# DE-110817_01.net
KiCad netlist of a schematic drawn in Altium Designer
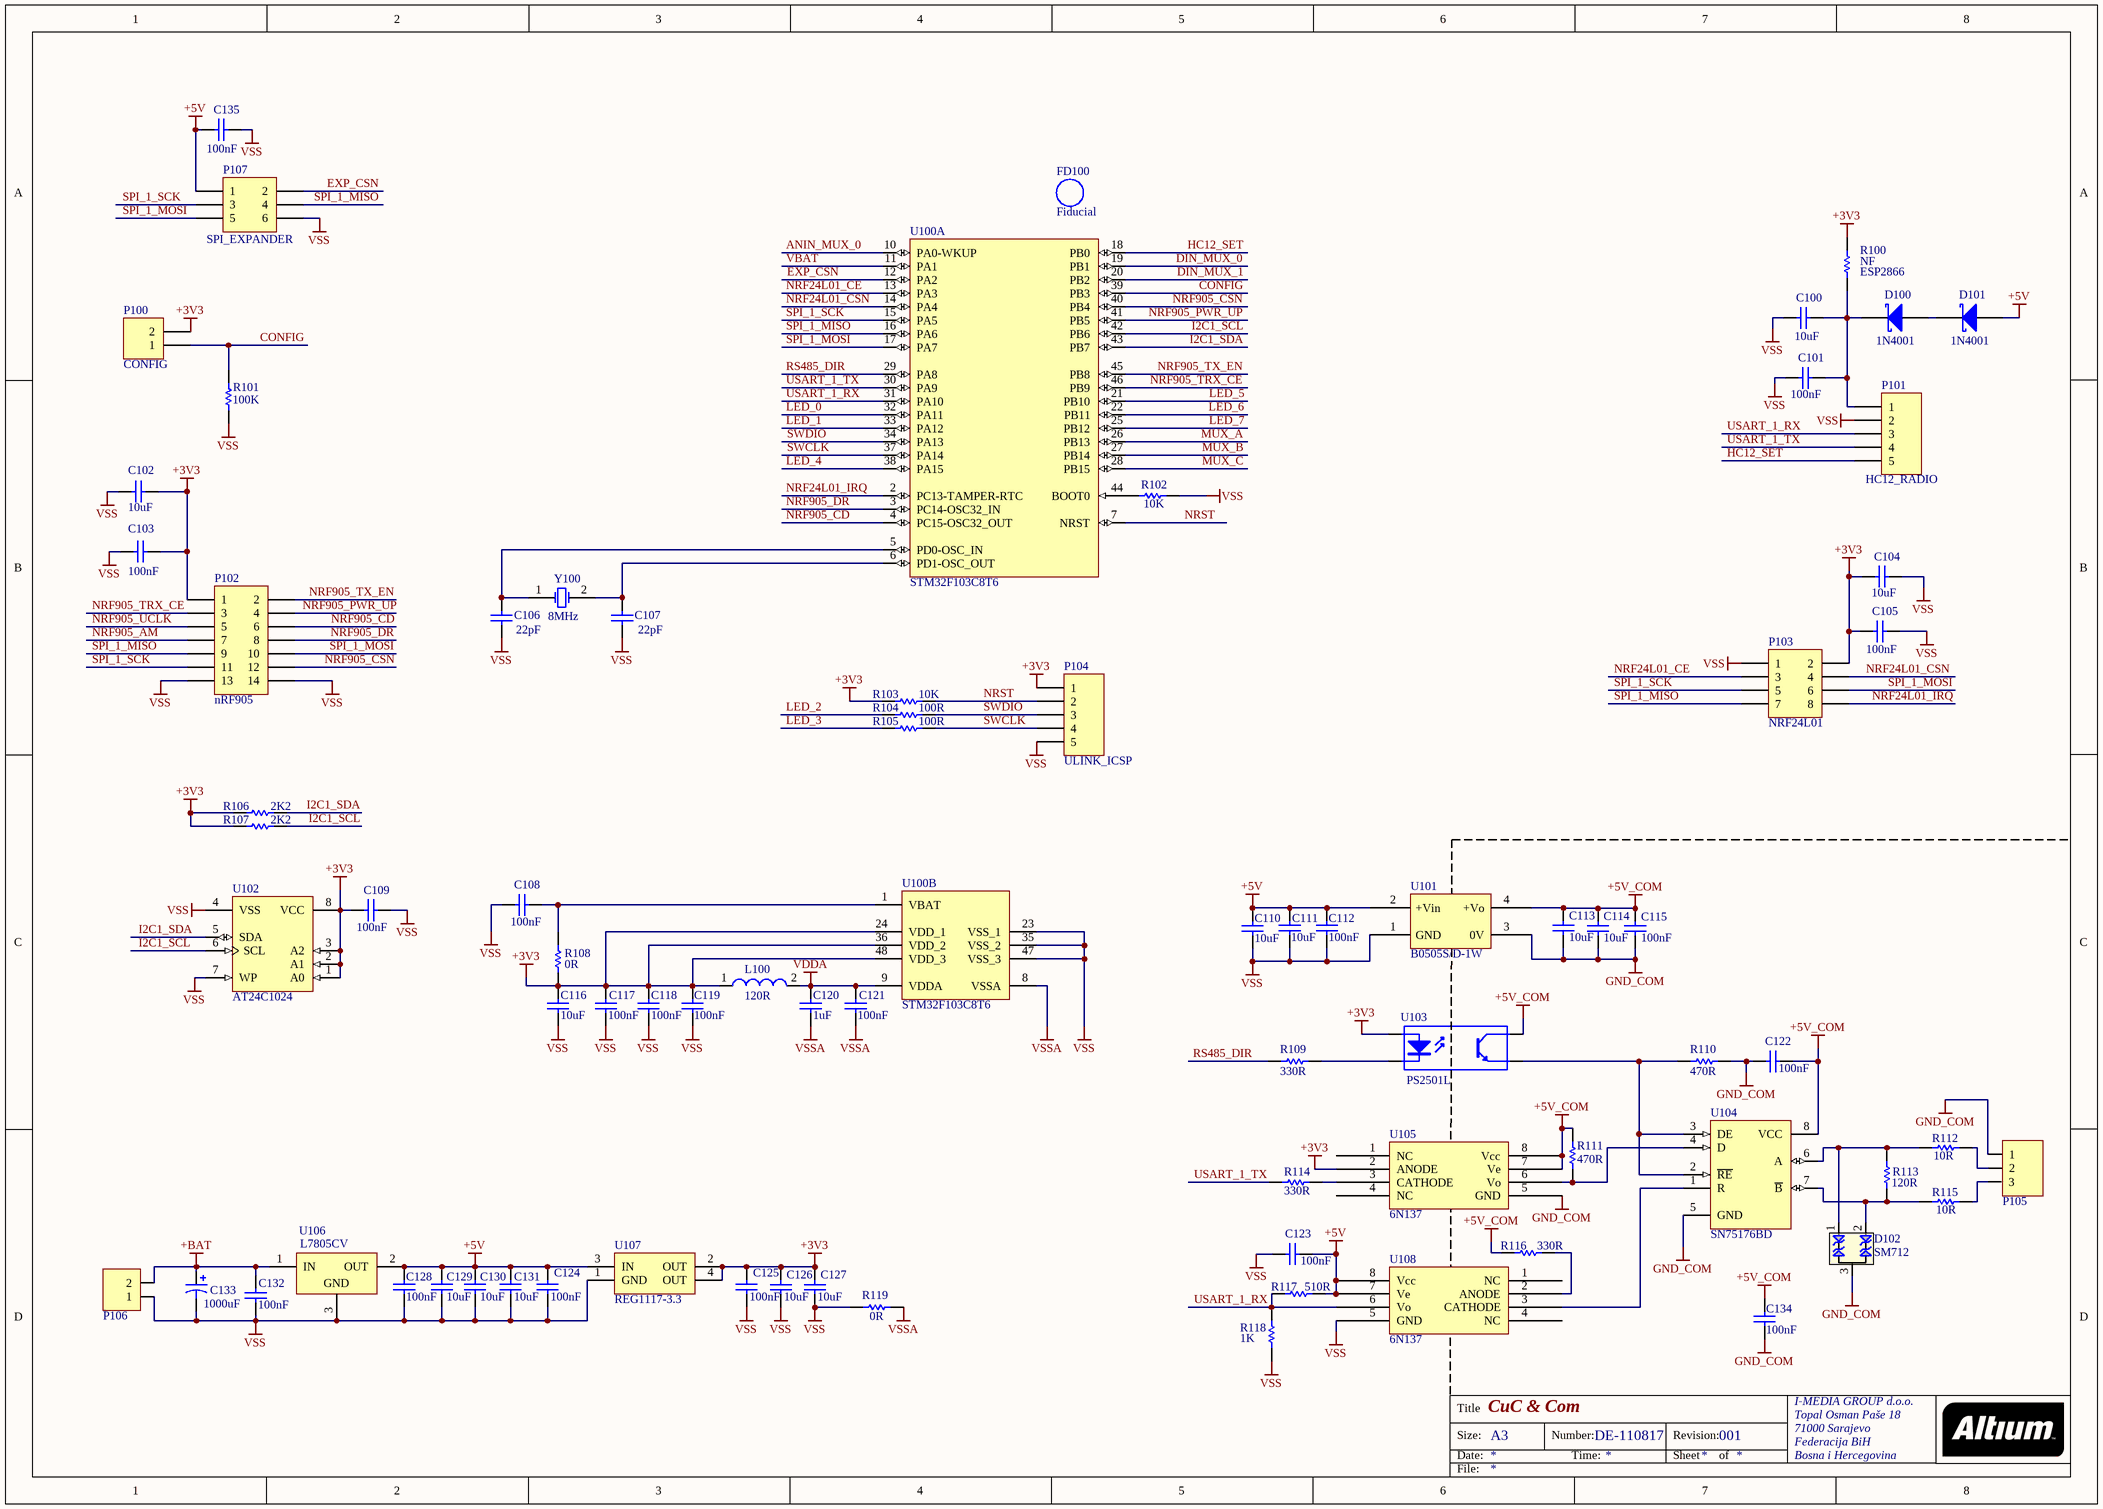
[diagram p0: DE-110817_01.SchDoc]

(export (version "E")
  (design (tool "Eeschema 10.0.6"))
  (components
    (comp (ref "C100")
      (value "10uF")
      (footprint "0805")
      (description "Ceramic Chip Capacitor - Standard")
      (fields (field (name "PUBLISHER") "Altium Limited"))
      (libsource (lib "KEMET Chip Capacitor") (part "C0805"))
    )
    (comp (ref "C101")
      (value "100nF")
      (footprint "0603")
      (description "Ceramic Chip Capacitor - Standard")
      (fields (field (name "PUBLISHER") "Altium Limited"))
      (libsource (lib "KEMET Chip Capacitor") (part "C0603"))
    )
    (comp (ref "C102")
      (value "10uF")
      (footprint "0805")
      (description "Ceramic Chip Capacitor - Standard")
      (fields (field (name "PUBLISHER") "Altium Limited"))
      (libsource (lib "KEMET Chip Capacitor") (part "C0805"))
    )
    (comp (ref "C103")
      (value "100nF")
      (footprint "0603")
      (description "Ceramic Chip Capacitor - Standard")
      (fields (field (name "PUBLISHER") "Altium Limited"))
      (libsource (lib "KEMET Chip Capacitor") (part "C0603"))
    )
    (comp (ref "C104")
      (value "10uF")
      (footprint "0805")
      (description "Ceramic Chip Capacitor - Standard")
      (fields (field (name "PUBLISHER") "Altium Limited"))
      (libsource (lib "KEMET Chip Capacitor") (part "C0805"))
    )
    (comp (ref "C105")
      (value "100nF")
      (footprint "0603")
      (description "Ceramic Chip Capacitor - Standard")
      (fields (field (name "PUBLISHER") "Altium Limited"))
      (libsource (lib "KEMET Chip Capacitor") (part "C0603"))
    )
    (comp (ref "C106")
      (value "22pF")
      (footprint "0603")
      (description "Ceramic Chip Capacitor - Standard")
      (fields (field (name "PUBLISHER") "Altium Limited"))
      (libsource (lib "KEMET Chip Capacitor") (part "C0603"))
    )
    (comp (ref "C107")
      (value "22pF")
      (footprint "0603")
      (description "Ceramic Chip Capacitor - Standard")
      (fields (field (name "PUBLISHER") "Altium Limited"))
      (libsource (lib "KEMET Chip Capacitor") (part "C0603"))
    )
    (comp (ref "C108")
      (value "100nF")
      (footprint "0603")
      (description "Ceramic Chip Capacitor - Standard")
      (fields (field (name "PUBLISHER") "Altium Limited"))
      (libsource (lib "KEMET Chip Capacitor") (part "C0603"))
    )
    (comp (ref "C109")
      (value "100nF")
      (footprint "0603")
      (description "Ceramic Chip Capacitor - Standard")
      (fields (field (name "PUBLISHER") "Altium Limited"))
      (libsource (lib "DE-251215") (part "C0603"))
    )
    (comp (ref "C110")
      (value "10uF")
      (footprint "0805")
      (description "Ceramic Chip Capacitor - Standard")
      (fields (field (name "PUBLISHER") "Altium Limited"))
      (libsource (lib "DE-110817") (part "C0805"))
    )
    (comp (ref "C111")
      (value "10uF")
      (footprint "0805")
      (description "Ceramic Chip Capacitor - Standard")
      (fields (field (name "PUBLISHER") "Altium Limited"))
      (libsource (lib "DE-110817") (part "C0805"))
    )
    (comp (ref "C112")
      (value "100nF")
      (footprint "0603")
      (description "Ceramic Chip Capacitor - Standard")
      (fields (field (name "PUBLISHER") "Altium Limited"))
      (libsource (lib "DE-110817") (part "C0603"))
    )
    (comp (ref "C113")
      (value "10uF")
      (footprint "0805")
      (description "Ceramic Chip Capacitor - Standard")
      (fields (field (name "PUBLISHER") "Altium Limited"))
      (libsource (lib "DE-110817") (part "C0805"))
    )
    (comp (ref "C114")
      (value "10uF")
      (footprint "0805")
      (description "Ceramic Chip Capacitor - Standard")
      (fields (field (name "PUBLISHER") "Altium Limited"))
      (libsource (lib "DE-110817") (part "C0805"))
    )
    (comp (ref "C115")
      (value "100nF")
      (footprint "0603")
      (description "Ceramic Chip Capacitor - Standard")
      (fields (field (name "PUBLISHER") "Altium Limited"))
      (libsource (lib "DE-110817") (part "C0603"))
    )
    (comp (ref "C116")
      (value "10uF")
      (footprint "0805")
      (description "Ceramic Chip Capacitor - Standard")
      (fields (field (name "PUBLISHER") "Altium Limited"))
      (libsource (lib "KEMET Chip Capacitor") (part "C0805"))
    )
    (comp (ref "C117")
      (value "100nF")
      (footprint "0603")
      (description "Ceramic Chip Capacitor - Standard")
      (fields (field (name "PUBLISHER") "Altium Limited"))
      (libsource (lib "KEMET Chip Capacitor") (part "C0603"))
    )
    (comp (ref "C118")
      (value "100nF")
      (footprint "0603")
      (description "Ceramic Chip Capacitor - Standard")
      (fields (field (name "PUBLISHER") "Altium Limited"))
      (libsource (lib "KEMET Chip Capacitor") (part "C0603"))
    )
    (comp (ref "C119")
      (value "100nF")
      (footprint "0603")
      (description "Ceramic Chip Capacitor - Standard")
      (fields (field (name "PUBLISHER") "Altium Limited"))
      (libsource (lib "KEMET Chip Capacitor") (part "C0603"))
    )
    (comp (ref "C120")
      (value "1uF")
      (footprint "0603")
      (description "Ceramic Chip Capacitor - Standard")
      (fields (field (name "PUBLISHER") "Altium Limited"))
      (libsource (lib "KEMET Chip Capacitor") (part "C0603"))
    )
    (comp (ref "C121")
      (value "100nF")
      (footprint "0603")
      (description "Ceramic Chip Capacitor - Standard")
      (fields (field (name "PUBLISHER") "Altium Limited"))
      (libsource (lib "KEMET Chip Capacitor") (part "C0603"))
    )
    (comp (ref "C122")
      (value "100nF")
      (footprint "0603")
      (description "Ceramic Chip Capacitor - Standard")
      (fields (field (name "PUBLISHER") "Altium Limited"))
      (libsource (lib "DE-251215") (part "C0603"))
    )
    (comp (ref "C123")
      (value "100nF")
      (footprint "0603")
      (description "Ceramic Chip Capacitor - Standard")
      (fields (field (name "PUBLISHER") "Altium Limited"))
      (libsource (lib "DE-251215") (part "C0603"))
    )
    (comp (ref "C124")
      (value "100nF")
      (footprint "0603")
      (description "Ceramic Chip Capacitor - Standard")
      (fields (field (name "PUBLISHER") "Altium Limited"))
      (libsource (lib "DE-251215") (part "C0603"))
    )
    (comp (ref "C125")
      (value "100nF")
      (footprint "0603")
      (description "Ceramic Chip Capacitor - Standard")
      (fields (field (name "PUBLISHER") "Altium Limited"))
      (libsource (lib "DE-251215") (part "C0603"))
    )
    (comp (ref "C126")
      (value "10uF")
      (footprint "0805")
      (description "Ceramic Chip Capacitor - Standard")
      (fields (field (name "PUBLISHER") "Altium Limited"))
      (libsource (lib "DE-251215") (part "C0805"))
    )
    (comp (ref "C127")
      (value "10uF")
      (footprint "0805")
      (description "Ceramic Chip Capacitor - Standard")
      (fields (field (name "PUBLISHER") "Altium Limited"))
      (libsource (lib "DE-251215") (part "C0805"))
    )
    (comp (ref "C128")
      (value "100nF")
      (footprint "0603")
      (description "Ceramic Chip Capacitor - Standard")
      (fields (field (name "PUBLISHER") "Altium Limited"))
      (libsource (lib "DE-251215") (part "C0603"))
    )
    (comp (ref "C129")
      (value "10uF")
      (footprint "0805")
      (description "Ceramic Chip Capacitor - Standard")
      (fields (field (name "PUBLISHER") "Altium Limited"))
      (libsource (lib "DE-251215") (part "C0805"))
    )
    (comp (ref "C130")
      (value "10uF")
      (footprint "0805")
      (description "Ceramic Chip Capacitor - Standard")
      (fields (field (name "PUBLISHER") "Altium Limited"))
      (libsource (lib "DE-251215") (part "C0805"))
    )
    (comp (ref "C131")
      (value "10uF")
      (footprint "0805")
      (description "Ceramic Chip Capacitor - Standard")
      (fields (field (name "PUBLISHER") "Altium Limited"))
      (libsource (lib "DE-200216_03") (part "C0805"))
    )
    (comp (ref "C132")
      (value "100nF")
      (footprint "0603")
      (description "Ceramic Chip Capacitor - Standard")
      (fields (field (name "PUBLISHER") "Altium Limited"))
      (libsource (lib "DE-251215") (part "C0603"))
    )
    (comp (ref "C133")
      (value "1000uF")
      (footprint "CAPPR5-10x16")
      (description "Aluminum Electrolytic Capacitor, Radial Style with Long Leads: 1000uF, 16V")
      (fields (field (name "PUBLISHER") "Altium Limited"))
      (libsource (lib "Vishay Roederstein Electrolytic Radial-Lead Capacitor") (part "EKA00DD410D00"))
    )
    (comp (ref "C134")
      (value "100nF")
      (footprint "0603")
      (description "Ceramic Chip Capacitor - Standard")
      (fields (field (name "PUBLISHER") "Altium Limited"))
      (libsource (lib "DE-251215") (part "C0603"))
    )
    (comp (ref "C135")
      (value "100nF")
      (footprint "0603")
      (description "Ceramic Chip Capacitor - Standard")
      (fields (field (name "PUBLISHER") "Altium Limited"))
      (libsource (lib "DE-110817") (part "C0603"))
    )
    (comp (ref "D100")
      (value "1N4001")
      (footprint "SMA")
      (description "Schottky Rectifier")
      (fields (field (name "PUBLISHER") "Altium Limited"))
      (libsource (lib "IR Rectifier - Schottky") (part "10MQ060N"))
    )
    (comp (ref "D101")
      (value "1N4001")
      (footprint "SMA")
      (description "Schottky Rectifier")
      (fields (field (name "PUBLISHER") "Altium Limited"))
      (libsource (lib "IR Rectifier - Schottky") (part "10MQ060N"))
    )
    (comp (ref "D102")
      (value "SM712")
      (footprint "SOT23_3L")
      (description "TVS Diode WE-TVS-Standard, VRWM=5.0V")
      (fields (field (name "PARTNUMBER") "824022"))
      (libsource (lib "WE-TVS TVS Diode-Standard Series") (part "824022"))
    )
    (comp (ref "FD100")
      (value "Fiducial")
      (footprint "Fiducial")
      (description "Fiduchial mark")
      (libsource (lib "DE-200216_02_1") (part "Fiduchial"))
    )
    (comp (ref "L100")
      (value "120R")
      (footprint "SMD-0805")
      (description "SMD EMI Suppression Ferrite Bead WE-CBF, Z = 120 Ohm")
      (fields (field (name "PARTNUMBER") "74279202"))
      (libsource (lib "WE-CBF SMD EMI Suppression Ferrite Bead") (part "74279202"))
    )
    (comp (ref "P100")
      (value "CONFIG")
      (footprint "HDR1X2")
      (description "Header, 2-Pin")
      (fields (field (name "PUBLISHER") "Altium Limited"))
      (libsource (lib "Miscellaneous Connectors") (part "Header 2"))
    )
    (comp (ref "P101")
      (value "HC12_RADIO")
      (footprint "HDR1X5")
      (description "Header, 5-Pin")
      (fields (field (name "PUBLISHER") "Altium Limited"))
      (libsource (lib "Miscellaneous Connectors") (part "Header 5"))
    )
    (comp (ref "P102")
      (value "nRF905")
      (footprint "HDR2X7")
      (description "Header, 7-Pin, Dual row")
      (fields (field (name "PUBLISHER") "Altium Limited"))
      (libsource (lib "Miscellaneous Connectors") (part "Header 7X2"))
    )
    (comp (ref "P103")
      (value "NRF24L01")
      (footprint "HDR2X4")
      (description "Header, 4-Pin, Dual row")
      (fields (field (name "PUBLISHER") "Altium Limited"))
      (libsource (lib "Miscellaneous Connectors") (part "Header 4X2"))
    )
    (comp (ref "P104")
      (value "ULINK_ICSP")
      (footprint "HDR1X5")
      (description "Header, 5-Pin")
      (fields (field (name "PUBLISHER") "Altium Limited"))
      (libsource (lib "Miscellaneous Connectors") (part "Header 5"))
    )
    (comp (ref "P105")
      (value "TERMINAL BLOK 3")
      (footprint "TERMINAL BLOK 3")
      (description "3 pinski terminal blok konektor")
      (libsource (lib "DE-110817") (part "TERMINAL BLOK 3"))
    )
    (comp (ref "P106")
      (value "TERMINAL BLOK 2")
      (footprint "TERMINAL BLOK 2")
      (description "2 pinski terminal blok")
      (libsource (lib "DE-130817") (part "TERMINAL BLOK 2"))
    )
    (comp (ref "P107")
      (value "SPI_EXPANDER")
      (footprint "HDR2X3")
      (description "Header, 3-Pin, Dual row")
      (fields (field (name "PUBLISHER") "Altium Limited"))
      (libsource (lib "Miscellaneous Connectors") (part "Header 3X2"))
    )
    (comp (ref "R100")
      (value "NF")
      (footprint "ERA-0603")
      (fields (field (name "PUBLISHER") "Altium Limited"))
      (libsource (lib "DE-200216_03") (part "ERAV"))
    )
    (comp (ref "R101")
      (value "100K")
      (footprint "ERA-0603")
      (fields (field (name "PUBLISHER") "Altium Limited"))
      (libsource (lib "Panasonic Resistor") (part "ERA3Y"))
    )
    (comp (ref "R102")
      (value "10K")
      (footprint "ERA-0603")
      (fields (field (name "PUBLISHER") "Altium Limited"))
      (libsource (lib "Panasonic Resistor") (part "ERA3Y"))
    )
    (comp (ref "R103")
      (value "10K")
      (footprint "ERA-0603")
      (fields (field (name "PUBLISHER") "Altium Limited"))
      (libsource (lib "Panasonic Resistor") (part "ERA3Y"))
    )
    (comp (ref "R104")
      (value "100R")
      (footprint "ERA-0603")
      (fields (field (name "PUBLISHER") "Altium Limited"))
      (libsource (lib "Panasonic Resistor") (part "ERA3Y"))
    )
    (comp (ref "R105")
      (value "100R")
      (footprint "ERA-0603")
      (fields (field (name "PUBLISHER") "Altium Limited"))
      (libsource (lib "Panasonic Resistor") (part "ERA3Y"))
    )
    (comp (ref "R106")
      (value "2K2")
      (footprint "ERA-0603")
      (fields (field (name "PUBLISHER") "Altium Limited"))
      (libsource (lib "Panasonic Resistor") (part "ERA3Y"))
    )
    (comp (ref "R107")
      (value "2K2")
      (footprint "ERA-0603")
      (fields (field (name "PUBLISHER") "Altium Limited"))
      (libsource (lib "Panasonic Resistor") (part "ERA3Y"))
    )
    (comp (ref "R108")
      (value "0R")
      (footprint "ERA-0603")
      (fields (field (name "PUBLISHER") "Altium Limited"))
      (libsource (lib "Panasonic Resistor") (part "ERA3Y"))
    )
    (comp (ref "R109")
      (value "330R")
      (footprint "ERA-0603")
      (fields (field (name "PUBLISHER") "Altium Limited"))
      (libsource (lib "DE-200216_01") (part "ERAV"))
    )
    (comp (ref "R110")
      (value "470R")
      (footprint "ERA-0603")
      (fields (field (name "PUBLISHER") "Altium Limited"))
      (libsource (lib "DE-200216_01") (part "ERAV"))
    )
    (comp (ref "R111")
      (value "470R")
      (footprint "ERA-0603")
      (fields (field (name "PUBLISHER") "Altium Limited"))
      (libsource (lib "DE-200216_01") (part "ERAV"))
    )
    (comp (ref "R112")
      (value "10R")
      (footprint "ERA-0805")
      (fields (field (name "PUBLISHER") "Altium Limited"))
      (libsource (lib "Panasonic Resistor") (part "ERA6Y"))
    )
    (comp (ref "R113")
      (value "120R")
      (footprint "ERA-0805")
      (fields (field (name "PUBLISHER") "Altium Limited"))
      (libsource (lib "Panasonic Resistor") (part "ERA6Y"))
    )
    (comp (ref "R114")
      (value "330R")
      (footprint "ERA-0603")
      (fields (field (name "PUBLISHER") "Altium Limited"))
      (libsource (lib "Panasonic Resistor") (part "ERA3Y"))
    )
    (comp (ref "R115")
      (value "10R")
      (footprint "ERA-0805")
      (fields (field (name "PUBLISHER") "Altium Limited"))
      (libsource (lib "Panasonic Resistor") (part "ERA6Y"))
    )
    (comp (ref "R116")
      (value "330R")
      (footprint "ERA-0603")
      (fields (field (name "PUBLISHER") "Altium Limited"))
      (libsource (lib "DE-200216_01") (part "ERAV"))
    )
    (comp (ref "R117")
      (value "510R")
      (footprint "ERA-0603")
      (fields (field (name "PUBLISHER") "Altium Limited"))
      (libsource (lib "DE-200216_01") (part "ERAV"))
    )
    (comp (ref "R118")
      (value "1K")
      (footprint "ERA-0603")
      (fields (field (name "PUBLISHER") "Altium Limited"))
      (libsource (lib "DE-200216_01") (part "ERAV"))
    )
    (comp (ref "R119")
      (value "0R")
      (footprint "ERA-0603")
      (fields (field (name "PUBLISHER") "Altium Limited"))
      (libsource (lib "DE-110817") (part "ERAV"))
    )
    (comp (ref "U100")
      (value "STM32F103C8T6")
      (footprint "STM-LQFP48_N")
      (libsource (lib "STMicroelectronics STM32 F1") (part "STM32F103C8T6"))
    )
    (comp (ref "U101")
      (value "B0505S/D-1W")
      (footprint "B0505S-1W")
      (description "1W isolated dc dc converter")
      (libsource (lib "DE-110817") (part "B0505S/D"))
    )
    (comp (ref "U102")
      (value "AT24C1024")
      (footprint "SOIC-SN8_N")
      (description "64Kbit, 400kHz, 1.7V, I2C Serial EEPROM, 8-Pin SOIC 150mil, Commercial Temperature")
      (fields (field (name "PUBLISHER") "Altium Limited"))
      (libsource (lib "Microchip Memory I2C Serial EEPROM") (part "24AA64/SN"))
    )
    (comp (ref "U103")
      (value "PS2501L")
      (footprint "SOP4")
      (description "4-Pin Phototransistor Optocoupler")
      (fields (field (name "PUBLISHER") "Altium Limited"))
      (libsource (lib "DE-200216_03") (part "PC817 optocoupler"))
    )
    (comp (ref "U104")
      (value "SN75176BD")
      (footprint "D008_L")
      (description "Differential Bus Transceiver")
      (fields (field (name "PUBLISHER") "Altium Limited"))
      (libsource (lib "DE-251215") (part "SN75176BD"))
    )
    (comp (ref "U105")
      (value "6N137")
      (footprint "SMD-8")
      (description "High CMR, High Speed TTL Compatibile Optocoupler")
      (libsource (lib "DE-110817") (part "6N137"))
    )
    (comp (ref "U106")
      (value "L7805CV")
      (footprint "TO220ABN")
      (description "Positive Voltage Regulator")
      (fields (field (name "PUBLISHER") "Altium Limited"))
      (libsource (lib "ST Power Mgt Voltage Regulator") (part "L7805CV"))
    )
    (comp (ref "U107")
      (value "REG1117-3.3")
      (footprint "ZZ311")
      (description "800mA and 1A Low Dropout Positive Regulator 2.85V, 3.3V, 5V, and Adjustable")
      (fields (field (name "PUBLISHER") "Altium Limited"))
      (libsource (lib "DE-251215") (part "REG1117-3.3"))
    )
    (comp (ref "U108")
      (value "6N137")
      (footprint "SMD-8")
      (description "High CMR, High Speed TTL Compatibile Optocoupler")
      (libsource (lib "") (part "6N137_1"))
    )
    (comp (ref "Y100")
      (value "8MHz")
      (footprint "HC49/4H_SMX")
      (description "Surface Mount Quartz Crystal")
      (fields (field (name "PUBLISHER") "Altium Limited"))
      (libsource (lib "C-MAC Crystal Oscillator") (part "HC49/4H_SMX"))
    )
  )
  (nets
    (net (code "1") (name "+3V3") (class "Default")
      (node (ref "C102") (pin "1") (pinfunction "1_1") (pintype "passive"))
      (node (ref "C103") (pin "1") (pinfunction "1_1") (pintype "passive"))
      (node (ref "C104") (pin "1") (pinfunction "1_1") (pintype "passive"))
      (node (ref "C105") (pin "1") (pinfunction "1_1") (pintype "passive"))
      (node (ref "C109") (pin "1") (pinfunction "1_1") (pintype "passive"))
      (node (ref "C116") (pin "2") (pinfunction "2_2") (pintype "passive"))
      (node (ref "C117") (pin "2") (pinfunction "2_2") (pintype "passive"))
      (node (ref "C118") (pin "2") (pinfunction "2_2") (pintype "passive"))
      (node (ref "C119") (pin "2") (pinfunction "2_2") (pintype "passive"))
      (node (ref "C125") (pin "2") (pinfunction "2_2") (pintype "passive"))
      (node (ref "C126") (pin "2") (pinfunction "2_2") (pintype "passive"))
      (node (ref "C127") (pin "2") (pinfunction "2_2") (pintype "passive"))
      (node (ref "L100") (pin "1") (pinfunction "1_1") (pintype "passive"))
      (node (ref "P100") (pin "2") (pinfunction "2_2") (pintype "passive"))
      (node (ref "P102") (pin "1") (pinfunction "1_1") (pintype "passive"))
      (node (ref "P103") (pin "2") (pinfunction "2_2") (pintype "passive"))
      (node (ref "P104") (pin "1") (pinfunction "1_1") (pintype "passive"))
      (node (ref "R100") (pin "2") (pinfunction "2_2") (pintype "passive"))
      (node (ref "R103") (pin "2") (pinfunction "2_2") (pintype "passive"))
      (node (ref "R106") (pin "1") (pinfunction "1_1") (pintype "passive"))
      (node (ref "R107") (pin "1") (pinfunction "1_1") (pintype "passive"))
      (node (ref "R108") (pin "2") (pinfunction "2_2") (pintype "passive"))
      (node (ref "U100") (pin "24") (pinfunction "VDD_1_24") (pintype "power_in"))
      (node (ref "U100") (pin "36") (pinfunction "VDD_2_36") (pintype "power_in"))
      (node (ref "U100") (pin "48") (pinfunction "VDD_3_48") (pintype "power_in"))
      (node (ref "U102") (pin "1") (pinfunction "A0_1") (pintype "input"))
      (node (ref "U102") (pin "2") (pinfunction "A1_2") (pintype "input"))
      (node (ref "U102") (pin "3") (pinfunction "A2_3") (pintype "input"))
      (node (ref "U102") (pin "8") (pinfunction "VCC_8") (pintype "power_in"))
      (node (ref "U103") (pin "1") (pinfunction "A_1") (pintype "passive"))
      (node (ref "U105") (pin "2") (pinfunction "ANODE_2") (pintype "passive"))
      (node (ref "U107") (pin "2") (pinfunction "OUT_2") (pintype "power_in"))
      (node (ref "U107") (pin "4") (pinfunction "OUT_4") (pintype "power_in"))
    )
    (net (code "2") (name "+5V") (class "Default")
      (node (ref "C110") (pin "2") (pinfunction "2_2") (pintype "passive"))
      (node (ref "C111") (pin "2") (pinfunction "2_2") (pintype "passive"))
      (node (ref "C112") (pin "2") (pinfunction "2_2") (pintype "passive"))
      (node (ref "C123") (pin "1") (pinfunction "1_1") (pintype "passive"))
      (node (ref "C124") (pin "2") (pinfunction "2_2") (pintype "passive"))
      (node (ref "C128") (pin "2") (pinfunction "2_2") (pintype "passive"))
      (node (ref "C129") (pin "2") (pinfunction "2_2") (pintype "passive"))
      (node (ref "C130") (pin "2") (pinfunction "2_2") (pintype "passive"))
      (node (ref "C131") (pin "2") (pinfunction "2_2") (pintype "passive"))
      (node (ref "C135") (pin "2") (pinfunction "2_2") (pintype "passive"))
      (node (ref "D101") (pin "1") (pinfunction "A_1") (pintype "passive"))
      (node (ref "P107") (pin "1") (pinfunction "1_1") (pintype "passive"))
      (node (ref "R117") (pin "1") (pinfunction "1_1") (pintype "passive"))
      (node (ref "U101") (pin "2") (pinfunction "+Vin_2") (pintype "passive"))
      (node (ref "U106") (pin "2") (pinfunction "OUT_2") (pintype "power_in"))
      (node (ref "U107") (pin "3") (pinfunction "IN_3") (pintype "power_in"))
      (node (ref "U108") (pin "7") (pinfunction "Ve_7") (pintype "passive"))
      (node (ref "U108") (pin "8") (pinfunction "Vcc_8") (pintype "passive"))
    )
    (net (code "3") (name "+5V_COM") (class "Default")
      (node (ref "C113") (pin "2") (pinfunction "2_2") (pintype "passive"))
      (node (ref "C114") (pin "2") (pinfunction "2_2") (pintype "passive"))
      (node (ref "C115") (pin "2") (pinfunction "2_2") (pintype "passive"))
      (node (ref "C122") (pin "2") (pinfunction "2_2") (pintype "passive"))
      (node (ref "C134") (pin "1") (pinfunction "1_1") (pintype "passive"))
      (node (ref "R111") (pin "1") (pinfunction "1_1") (pintype "passive"))
      (node (ref "R116") (pin "2") (pinfunction "2_2") (pintype "passive"))
      (node (ref "U101") (pin "4") (pinfunction "+Vo_4") (pintype "passive"))
      (node (ref "U103") (pin "4") (pinfunction "C_4") (pintype "passive"))
      (node (ref "U104") (pin "8") (pinfunction "VCC_8") (pintype "power_in"))
      (node (ref "U105") (pin "7") (pinfunction "Ve_7") (pintype "passive"))
      (node (ref "U105") (pin "8") (pinfunction "Vcc_8") (pintype "passive"))
    )
    (net (code "4") (name "+BAT") (class "Default")
      (node (ref "C132") (pin "2") (pinfunction "2_2") (pintype "passive"))
      (node (ref "C133") (pin "1") (pinfunction "1_1") (pintype "passive"))
      (node (ref "P106") (pin "2") (pinfunction "2_2") (pintype "passive"))
      (node (ref "U106") (pin "1") (pinfunction "IN_1") (pintype "power_in"))
    )
    (net (code "5") (name "/ANIN_MUX_0") (class "Default")
      (node (ref "U100") (pin "10") (pinfunction "PA0-WKUP_10") (pintype "bidirectional"))
    )
    (net (code "6") (name "/CONFIG") (class "Default")
      (node (ref "P100") (pin "1") (pinfunction "1_1") (pintype "passive"))
      (node (ref "R101") (pin "2") (pinfunction "2_2") (pintype "passive"))
      (node (ref "U100") (pin "39") (pinfunction "PB3_39") (pintype "bidirectional"))
    )
    (net (code "7") (name "/DIN_MUX_0") (class "Default")
      (node (ref "U100") (pin "19") (pinfunction "PB1_19") (pintype "bidirectional"))
    )
    (net (code "8") (name "/DIN_MUX_1") (class "Default")
      (node (ref "U100") (pin "20") (pinfunction "PB2_20") (pintype "bidirectional"))
    )
    (net (code "9") (name "/EXP_CSN") (class "Default")
      (node (ref "P107") (pin "2") (pinfunction "2_2") (pintype "passive"))
      (node (ref "U100") (pin "12") (pinfunction "PA2_12") (pintype "bidirectional"))
    )
    (net (code "10") (name "/HC12_SET") (class "Default")
      (node (ref "P101") (pin "5") (pinfunction "5_5") (pintype "passive"))
      (node (ref "U100") (pin "18") (pinfunction "PB0_18") (pintype "bidirectional"))
    )
    (net (code "11") (name "/I2C1_SCL") (class "Default")
      (node (ref "R107") (pin "2") (pinfunction "2_2") (pintype "passive"))
      (node (ref "U100") (pin "42") (pinfunction "PB6_42") (pintype "bidirectional"))
      (node (ref "U102") (pin "6") (pinfunction "SCL_6") (pintype "input"))
    )
    (net (code "12") (name "/I2C1_SDA") (class "Default")
      (node (ref "R106") (pin "2") (pinfunction "2_2") (pintype "passive"))
      (node (ref "U100") (pin "43") (pinfunction "PB7_43") (pintype "bidirectional"))
      (node (ref "U102") (pin "5") (pinfunction "SDA_5") (pintype "bidirectional"))
    )
    (net (code "13") (name "/LED_0") (class "Default")
      (node (ref "U100") (pin "32") (pinfunction "PA11_32") (pintype "bidirectional"))
    )
    (net (code "14") (name "/LED_1") (class "Default")
      (node (ref "U100") (pin "33") (pinfunction "PA12_33") (pintype "bidirectional"))
    )
    (net (code "15") (name "/LED_2") (class "Default")
      (node (ref "R104") (pin "2") (pinfunction "2_2") (pintype "passive"))
    )
    (net (code "16") (name "/LED_3") (class "Default")
      (node (ref "R105") (pin "2") (pinfunction "2_2") (pintype "passive"))
    )
    (net (code "17") (name "/LED_4") (class "Default")
      (node (ref "U100") (pin "38") (pinfunction "PA15_38") (pintype "bidirectional"))
    )
    (net (code "18") (name "/LED_5") (class "Default")
      (node (ref "U100") (pin "21") (pinfunction "PB10_21") (pintype "bidirectional"))
    )
    (net (code "19") (name "/LED_6") (class "Default")
      (node (ref "U100") (pin "22") (pinfunction "PB11_22") (pintype "bidirectional"))
    )
    (net (code "20") (name "/LED_7") (class "Default")
      (node (ref "U100") (pin "25") (pinfunction "PB12_25") (pintype "bidirectional"))
    )
    (net (code "21") (name "/MUX_A") (class "Default")
      (node (ref "U100") (pin "26") (pinfunction "PB13_26") (pintype "bidirectional"))
    )
    (net (code "22") (name "/MUX_B") (class "Default")
      (node (ref "U100") (pin "27") (pinfunction "PB14_27") (pintype "bidirectional"))
    )
    (net (code "23") (name "/MUX_C") (class "Default")
      (node (ref "U100") (pin "28") (pinfunction "PB15_28") (pintype "bidirectional"))
    )
    (net (code "24") (name "/NRF24L01_CE") (class "Default")
      (node (ref "P103") (pin "3") (pinfunction "3_3") (pintype "passive"))
      (node (ref "U100") (pin "13") (pinfunction "PA3_13") (pintype "bidirectional"))
    )
    (net (code "25") (name "/NRF24L01_CSN") (class "Default")
      (node (ref "P103") (pin "4") (pinfunction "4_4") (pintype "passive"))
      (node (ref "U100") (pin "14") (pinfunction "PA4_14") (pintype "bidirectional"))
    )
    (net (code "26") (name "/NRF24L01_IRQ") (class "Default")
      (node (ref "P103") (pin "8") (pinfunction "8_8") (pintype "passive"))
      (node (ref "U100") (pin "2") (pinfunction "PC13-TAMPER-RTC_2") (pintype "bidirectional"))
    )
    (net (code "27") (name "/NRF905_AM") (class "Default")
      (node (ref "P102") (pin "7") (pinfunction "7_7") (pintype "passive"))
    )
    (net (code "28") (name "/NRF905_CD") (class "Default")
      (node (ref "P102") (pin "6") (pinfunction "6_6") (pintype "passive"))
      (node (ref "U100") (pin "4") (pinfunction "PC15-OSC32_OUT_4") (pintype "bidirectional"))
    )
    (net (code "29") (name "/NRF905_CSN") (class "Default")
      (node (ref "P102") (pin "12") (pinfunction "12_12") (pintype "passive"))
      (node (ref "U100") (pin "40") (pinfunction "PB4_40") (pintype "bidirectional"))
    )
    (net (code "30") (name "/NRF905_DR") (class "Default")
      (node (ref "P102") (pin "8") (pinfunction "8_8") (pintype "passive"))
      (node (ref "U100") (pin "3") (pinfunction "PC14-OSC32_IN_3") (pintype "bidirectional"))
    )
    (net (code "31") (name "/NRF905_PWR_UP") (class "Default")
      (node (ref "P102") (pin "4") (pinfunction "4_4") (pintype "passive"))
      (node (ref "U100") (pin "41") (pinfunction "PB5_41") (pintype "bidirectional"))
    )
    (net (code "32") (name "/NRF905_TRX_CE") (class "Default")
      (node (ref "P102") (pin "3") (pinfunction "3_3") (pintype "passive"))
      (node (ref "U100") (pin "46") (pinfunction "PB9_46") (pintype "bidirectional"))
    )
    (net (code "33") (name "/NRF905_TX_EN") (class "Default")
      (node (ref "P102") (pin "2") (pinfunction "2_2") (pintype "passive"))
      (node (ref "U100") (pin "45") (pinfunction "PB8_45") (pintype "bidirectional"))
    )
    (net (code "34") (name "/NRF905_UCLK") (class "Default")
      (node (ref "P102") (pin "5") (pinfunction "5_5") (pintype "passive"))
    )
    (net (code "35") (name "/NRST") (class "Default")
      (node (ref "P104") (pin "2") (pinfunction "2_2") (pintype "passive"))
      (node (ref "R103") (pin "1") (pinfunction "1_1") (pintype "passive"))
      (node (ref "U100") (pin "7") (pinfunction "NRST_7") (pintype "bidirectional"))
    )
    (net (code "36") (name "/RS485_DIR") (class "Default")
      (node (ref "R109") (pin "2") (pinfunction "2_2") (pintype "passive"))
      (node (ref "U100") (pin "29") (pinfunction "PA8_29") (pintype "bidirectional"))
    )
    (net (code "37") (name "/SPI_1_MISO") (class "Default")
      (node (ref "P102") (pin "9") (pinfunction "9_9") (pintype "passive"))
      (node (ref "P103") (pin "7") (pinfunction "7_7") (pintype "passive"))
      (node (ref "P107") (pin "4") (pinfunction "4_4") (pintype "passive"))
      (node (ref "U100") (pin "16") (pinfunction "PA6_16") (pintype "bidirectional"))
    )
    (net (code "38") (name "/SPI_1_MOSI") (class "Default")
      (node (ref "P102") (pin "10") (pinfunction "10_10") (pintype "passive"))
      (node (ref "P103") (pin "6") (pinfunction "6_6") (pintype "passive"))
      (node (ref "P107") (pin "5") (pinfunction "5_5") (pintype "passive"))
      (node (ref "U100") (pin "17") (pinfunction "PA7_17") (pintype "bidirectional"))
    )
    (net (code "39") (name "/SPI_1_SCK") (class "Default")
      (node (ref "P102") (pin "11") (pinfunction "11_11") (pintype "passive"))
      (node (ref "P103") (pin "5") (pinfunction "5_5") (pintype "passive"))
      (node (ref "P107") (pin "3") (pinfunction "3_3") (pintype "passive"))
      (node (ref "U100") (pin "15") (pinfunction "PA5_15") (pintype "bidirectional"))
    )
    (net (code "40") (name "/SWCLK") (class "Default")
      (node (ref "P104") (pin "4") (pinfunction "4_4") (pintype "passive"))
      (node (ref "R105") (pin "1") (pinfunction "1_1") (pintype "passive"))
      (node (ref "U100") (pin "37") (pinfunction "PA14_37") (pintype "bidirectional"))
    )
    (net (code "41") (name "/SWDIO") (class "Default")
      (node (ref "P104") (pin "3") (pinfunction "3_3") (pintype "passive"))
      (node (ref "R104") (pin "1") (pinfunction "1_1") (pintype "passive"))
      (node (ref "U100") (pin "34") (pinfunction "PA13_34") (pintype "bidirectional"))
    )
    (net (code "42") (name "/USART_1_RX") (class "Default")
      (node (ref "P101") (pin "3") (pinfunction "3_3") (pintype "passive"))
      (node (ref "R117") (pin "2") (pinfunction "2_2") (pintype "passive"))
      (node (ref "R118") (pin "2") (pinfunction "2_2") (pintype "passive"))
      (node (ref "U100") (pin "31") (pinfunction "PA10_31") (pintype "bidirectional"))
      (node (ref "U108") (pin "6") (pinfunction "Vo_6") (pintype "passive"))
    )
    (net (code "43") (name "/USART_1_TX") (class "Default")
      (node (ref "P101") (pin "4") (pinfunction "4_4") (pintype "passive"))
      (node (ref "R114") (pin "1") (pinfunction "1_1") (pintype "passive"))
      (node (ref "U100") (pin "30") (pinfunction "PA9_30") (pintype "bidirectional"))
    )
    (net (code "44") (name "/VBAT") (class "Default")
      (node (ref "U100") (pin "11") (pinfunction "PA1_11") (pintype "bidirectional"))
    )
    (net (code "45") (name "GND_COM") (class "Default")
      (node (ref "C113") (pin "1") (pinfunction "1_1") (pintype "passive"))
      (node (ref "C114") (pin "1") (pinfunction "1_1") (pintype "passive"))
      (node (ref "C115") (pin "1") (pinfunction "1_1") (pintype "passive"))
      (node (ref "C122") (pin "1") (pinfunction "1_1") (pintype "passive"))
      (node (ref "C134") (pin "2") (pinfunction "2_2") (pintype "passive"))
      (node (ref "D102") (pin "3") (pinfunction "GND_3") (pintype "passive"))
      (node (ref "P105") (pin "1") (pinfunction "1_1") (pintype "passive"))
      (node (ref "R110") (pin "2") (pinfunction "2_2") (pintype "passive"))
      (node (ref "U101") (pin "3") (pinfunction "0V_3") (pintype "passive"))
      (node (ref "U104") (pin "5") (pinfunction "GND_5") (pintype "power_in"))
      (node (ref "U105") (pin "5") (pinfunction "GND_5") (pintype "passive"))
    )
    (net (code "46") (name "Net-(D100-A)") (class "Default")
      (node (ref "D100") (pin "1") (pinfunction "A_1") (pintype "passive"))
      (node (ref "D101") (pin "2") (pinfunction "K_2") (pintype "passive"))
    )
    (net (code "47") (name "Net-(D100-K)") (class "Default")
      (node (ref "C100") (pin "1") (pinfunction "1_1") (pintype "passive"))
      (node (ref "C101") (pin "1") (pinfunction "1_1") (pintype "passive"))
      (node (ref "D100") (pin "2") (pinfunction "K_2") (pintype "passive"))
      (node (ref "P101") (pin "1") (pinfunction "1_1") (pintype "passive"))
      (node (ref "R100") (pin "1") (pinfunction "1_1") (pintype "passive"))
    )
    (net (code "48") (name "Net-(P105-Pad2)") (class "Default")
      (node (ref "P105") (pin "2") (pinfunction "2_2") (pintype "passive"))
      (node (ref "R112") (pin "2") (pinfunction "2_2") (pintype "passive"))
    )
    (net (code "49") (name "Net-(P105-Pad3)") (class "Default")
      (node (ref "P105") (pin "3") (pinfunction "3_3") (pintype "passive"))
      (node (ref "R115") (pin "2") (pinfunction "2_2") (pintype "passive"))
    )
    (net (code "50") (name "Net-(U100A-BOOT0)") (class "Default")
      (node (ref "R102") (pin "1") (pinfunction "1_1") (pintype "passive"))
      (node (ref "U100") (pin "44") (pinfunction "BOOT0_44") (pintype "input"))
    )
    (net (code "51") (name "Net-(U100A-PD0-OSC_IN)") (class "Default")
      (node (ref "C106") (pin "2") (pinfunction "2_2") (pintype "passive"))
      (node (ref "U100") (pin "5") (pinfunction "PD0-OSC_IN_5") (pintype "bidirectional"))
      (node (ref "Y100") (pin "1") (pinfunction "OSC1_1") (pintype "passive"))
    )
    (net (code "52") (name "Net-(U100A-PD1-OSC_OUT)") (class "Default")
      (node (ref "C107") (pin "2") (pinfunction "2_2") (pintype "passive"))
      (node (ref "U100") (pin "6") (pinfunction "PD1-OSC_OUT_6") (pintype "bidirectional"))
      (node (ref "Y100") (pin "2") (pinfunction "OSC2_2") (pintype "passive"))
    )
    (net (code "53") (name "Net-(U100B-VBAT)") (class "Default")
      (node (ref "C108") (pin "1") (pinfunction "1_1") (pintype "passive"))
      (node (ref "R108") (pin "1") (pinfunction "1_1") (pintype "passive"))
      (node (ref "U100") (pin "1") (pinfunction "VBAT_1") (pintype "power_in"))
    )
    (net (code "54") (name "Net-(U103-E)") (class "Default")
      (node (ref "R110") (pin "1") (pinfunction "1_1") (pintype "passive"))
      (node (ref "U103") (pin "3") (pinfunction "E_3") (pintype "passive"))
      (node (ref "U104") (pin "2") (pinfunction "~{RE}_2") (pintype "input"))
      (node (ref "U104") (pin "3") (pinfunction "DE_3") (pintype "input"))
    )
    (net (code "55") (name "Net-(U103-K)") (class "Default")
      (node (ref "R109") (pin "1") (pinfunction "1_1") (pintype "passive"))
      (node (ref "U103") (pin "2") (pinfunction "K_2") (pintype "passive"))
    )
    (net (code "56") (name "Net-(U104-A)") (class "Default")
      (node (ref "D102") (pin "1") (pinfunction "I/O_1") (pintype "passive"))
      (node (ref "R112") (pin "1") (pinfunction "1_1") (pintype "passive"))
      (node (ref "R113") (pin "2") (pinfunction "2_2") (pintype "passive"))
      (node (ref "U104") (pin "6") (pinfunction "A_6") (pintype "bidirectional"))
    )
    (net (code "57") (name "Net-(U104-D)") (class "Default")
      (node (ref "R111") (pin "2") (pinfunction "2_2") (pintype "passive"))
      (node (ref "U104") (pin "4") (pinfunction "D_4") (pintype "input"))
      (node (ref "U105") (pin "6") (pinfunction "Vo_6") (pintype "passive"))
    )
    (net (code "58") (name "Net-(U104-R)") (class "Default")
      (node (ref "U104") (pin "1") (pinfunction "R_1") (pintype "tri_state"))
      (node (ref "U108") (pin "3") (pinfunction "CATHODE_3") (pintype "passive"))
    )
    (net (code "59") (name "Net-(U104-~{B})") (class "Default")
      (node (ref "D102") (pin "2") (pinfunction "I/O_2") (pintype "passive"))
      (node (ref "R113") (pin "1") (pinfunction "1_1") (pintype "passive"))
      (node (ref "R115") (pin "1") (pinfunction "1_1") (pintype "passive"))
      (node (ref "U104") (pin "7") (pinfunction "~{B}_7") (pintype "bidirectional"))
    )
    (net (code "60") (name "Net-(U105-CATHODE)") (class "Default")
      (node (ref "R114") (pin "2") (pinfunction "2_2") (pintype "passive"))
      (node (ref "U105") (pin "3") (pinfunction "CATHODE_3") (pintype "passive"))
    )
    (net (code "61") (name "Net-(U108-ANODE)") (class "Default")
      (node (ref "R116") (pin "1") (pinfunction "1_1") (pintype "passive"))
      (node (ref "U108") (pin "2") (pinfunction "ANODE_2") (pintype "passive"))
    )
    (net (code "62") (name "VDDA") (class "Default")
      (node (ref "C120") (pin "2") (pinfunction "2_2") (pintype "passive"))
      (node (ref "C121") (pin "2") (pinfunction "2_2") (pintype "passive"))
      (node (ref "L100") (pin "2") (pinfunction "2_2") (pintype "passive"))
      (node (ref "U100") (pin "9") (pinfunction "VDDA_9") (pintype "power_in"))
    )
    (net (code "63") (name "VSS") (class "Default")
      (node (ref "C100") (pin "2") (pinfunction "2_2") (pintype "passive"))
      (node (ref "C101") (pin "2") (pinfunction "2_2") (pintype "passive"))
      (node (ref "C102") (pin "2") (pinfunction "2_2") (pintype "passive"))
      (node (ref "C103") (pin "2") (pinfunction "2_2") (pintype "passive"))
      (node (ref "C104") (pin "2") (pinfunction "2_2") (pintype "passive"))
      (node (ref "C105") (pin "2") (pinfunction "2_2") (pintype "passive"))
      (node (ref "C106") (pin "1") (pinfunction "1_1") (pintype "passive"))
      (node (ref "C107") (pin "1") (pinfunction "1_1") (pintype "passive"))
      (node (ref "C108") (pin "2") (pinfunction "2_2") (pintype "passive"))
      (node (ref "C109") (pin "2") (pinfunction "2_2") (pintype "passive"))
      (node (ref "C110") (pin "1") (pinfunction "1_1") (pintype "passive"))
      (node (ref "C111") (pin "1") (pinfunction "1_1") (pintype "passive"))
      (node (ref "C112") (pin "1") (pinfunction "1_1") (pintype "passive"))
      (node (ref "C116") (pin "1") (pinfunction "1_1") (pintype "passive"))
      (node (ref "C117") (pin "1") (pinfunction "1_1") (pintype "passive"))
      (node (ref "C118") (pin "1") (pinfunction "1_1") (pintype "passive"))
      (node (ref "C119") (pin "1") (pinfunction "1_1") (pintype "passive"))
      (node (ref "C123") (pin "2") (pinfunction "2_2") (pintype "passive"))
      (node (ref "C124") (pin "1") (pinfunction "1_1") (pintype "passive"))
      (node (ref "C125") (pin "1") (pinfunction "1_1") (pintype "passive"))
      (node (ref "C126") (pin "1") (pinfunction "1_1") (pintype "passive"))
      (node (ref "C127") (pin "1") (pinfunction "1_1") (pintype "passive"))
      (node (ref "C128") (pin "1") (pinfunction "1_1") (pintype "passive"))
      (node (ref "C129") (pin "1") (pinfunction "1_1") (pintype "passive"))
      (node (ref "C130") (pin "1") (pinfunction "1_1") (pintype "passive"))
      (node (ref "C131") (pin "1") (pinfunction "1_1") (pintype "passive"))
      (node (ref "C132") (pin "1") (pinfunction "1_1") (pintype "passive"))
      (node (ref "C133") (pin "2") (pinfunction "2_2") (pintype "passive"))
      (node (ref "C135") (pin "1") (pinfunction "1_1") (pintype "passive"))
      (node (ref "P101") (pin "2") (pinfunction "2_2") (pintype "passive"))
      (node (ref "P102") (pin "13") (pinfunction "13_13") (pintype "passive"))
      (node (ref "P102") (pin "14") (pinfunction "14_14") (pintype "passive"))
      (node (ref "P103") (pin "1") (pinfunction "1_1") (pintype "passive"))
      (node (ref "P104") (pin "5") (pinfunction "5_5") (pintype "passive"))
      (node (ref "P106") (pin "1") (pinfunction "1_1") (pintype "passive"))
      (node (ref "P107") (pin "6") (pinfunction "6_6") (pintype "passive"))
      (node (ref "R101") (pin "1") (pinfunction "1_1") (pintype "passive"))
      (node (ref "R102") (pin "2") (pinfunction "2_2") (pintype "passive"))
      (node (ref "R118") (pin "1") (pinfunction "1_1") (pintype "passive"))
      (node (ref "R119") (pin "1") (pinfunction "1_1") (pintype "passive"))
      (node (ref "U100") (pin "23") (pinfunction "VSS_1_23") (pintype "power_in"))
      (node (ref "U100") (pin "35") (pinfunction "VSS_2_35") (pintype "power_in"))
      (node (ref "U100") (pin "47") (pinfunction "VSS_3_47") (pintype "power_in"))
      (node (ref "U101") (pin "1") (pinfunction "GND_1") (pintype "passive"))
      (node (ref "U102") (pin "4") (pinfunction "VSS_4") (pintype "power_in"))
      (node (ref "U102") (pin "7") (pinfunction "WP_7") (pintype "input"))
      (node (ref "U106") (pin "3") (pinfunction "GND_3") (pintype "power_in"))
      (node (ref "U107") (pin "1") (pinfunction "GND_1") (pintype "power_in"))
      (node (ref "U108") (pin "5") (pinfunction "GND_5") (pintype "passive"))
    )
    (net (code "64") (name "VSSA") (class "Default")
      (node (ref "C120") (pin "1") (pinfunction "1_1") (pintype "passive"))
      (node (ref "C121") (pin "1") (pinfunction "1_1") (pintype "passive"))
      (node (ref "R119") (pin "2") (pinfunction "2_2") (pintype "passive"))
      (node (ref "U100") (pin "8") (pinfunction "VSSA_8") (pintype "power_in"))
    )
    (net (code "65") (name "unconnected-(U105-NC-Pad1)") (class "Default")
      (node (ref "U105") (pin "1") (pinfunction "NC_1") (pintype "passive"))
    )
    (net (code "66") (name "unconnected-(U105-NC-Pad4)") (class "Default")
      (node (ref "U105") (pin "4") (pinfunction "NC_4") (pintype "passive"))
    )
    (net (code "67") (name "unconnected-(U108-NC-Pad1)") (class "Default")
      (node (ref "U108") (pin "1") (pinfunction "NC_1") (pintype "passive"))
    )
    (net (code "68") (name "unconnected-(U108-NC-Pad4)") (class "Default")
      (node (ref "U108") (pin "4") (pinfunction "NC_4") (pintype "passive"))
    )
  )
)
